# PCB.net
KiCad netlist of a schematic drawn in EAGLE
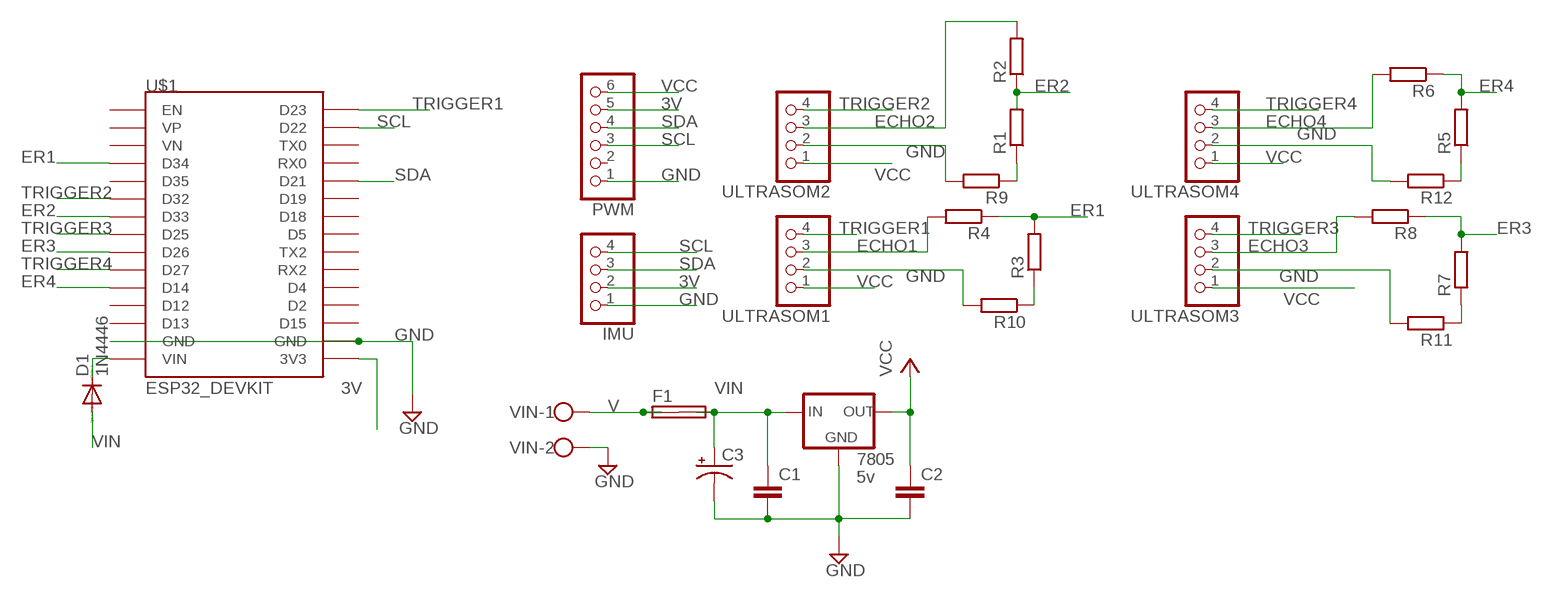
[diagram p0: schematic, sheet 1]

(export (version "E")
  (design (tool "Eeschema 10.0.6"))
  (components
    (comp (ref "7805")
      (value "5v")
      (footprint "eagle-import:78MXXS")
      (libsource (lib "eagle-import") (part "78MXXS"))
    )
    (comp (ref "C1")
      (value "C-EU025-024X044")
      (footprint "eagle-import:C025-024X044")
      (libsource (lib "eagle-import") (part "C-EU025-024X044"))
    )
    (comp (ref "C2")
      (value "C-EU025-024X044")
      (footprint "eagle-import:C025-024X044")
      (libsource (lib "eagle-import") (part "C-EU025-024X044"))
    )
    (comp (ref "C3")
      (value "CPOL-USE2-5")
      (footprint "eagle-import:E2-5")
      (libsource (lib "eagle-import") (part "CPOL-USE2-5"))
    )
    (comp (ref "D1")
      (value "1N4446")
      (footprint "eagle-import:DO35-10")
      (libsource (lib "eagle-import") (part "1N4446"))
    )
    (comp (ref "F1")
      (value "SHK20L")
      (footprint "eagle-import:SHK20L")
      (libsource (lib "eagle-import") (part "SHK20L"))
    )
    (comp (ref "IMU")
      (value "PINHD-1X4")
      (footprint "eagle-import:1X04")
      (libsource (lib "eagle-import") (part "PINHD-1X4"))
    )
    (comp (ref "PWM")
      (value "PINHD-1X6")
      (footprint "eagle-import:1X06")
      (libsource (lib "eagle-import") (part "PINHD-1X6"))
    )
    (comp (ref "R1")
      (value "R-EU_0207/7")
      (footprint "eagle-import:0207_7")
      (libsource (lib "eagle-import") (part "R-EU_0207/7"))
    )
    (comp (ref "R2")
      (value "R-EU_0207/7")
      (footprint "eagle-import:0207_7")
      (libsource (lib "eagle-import") (part "R-EU_0207/7"))
    )
    (comp (ref "R3")
      (value "R-EU_0207/7")
      (footprint "eagle-import:0207_7")
      (libsource (lib "eagle-import") (part "R-EU_0207/7"))
    )
    (comp (ref "R4")
      (value "R-EU_0207/7")
      (footprint "eagle-import:0207_7")
      (libsource (lib "eagle-import") (part "R-EU_0207/7"))
    )
    (comp (ref "R5")
      (value "R-EU_0207/7")
      (footprint "eagle-import:0207_7")
      (libsource (lib "eagle-import") (part "R-EU_0207/7"))
    )
    (comp (ref "R6")
      (value "R-EU_0207/7")
      (footprint "eagle-import:0207_7")
      (libsource (lib "eagle-import") (part "R-EU_0207/7"))
    )
    (comp (ref "R7")
      (value "R-EU_0207/7")
      (footprint "eagle-import:0207_7")
      (libsource (lib "eagle-import") (part "R-EU_0207/7"))
    )
    (comp (ref "R8")
      (value "R-EU_0207/7")
      (footprint "eagle-import:0207_7")
      (libsource (lib "eagle-import") (part "R-EU_0207/7"))
    )
    (comp (ref "R9")
      (value "R-EU_0207/7")
      (footprint "eagle-import:0207_7")
      (libsource (lib "eagle-import") (part "R-EU_0207/7"))
    )
    (comp (ref "R10")
      (value "R-EU_0207/7")
      (footprint "eagle-import:0207_7")
      (libsource (lib "eagle-import") (part "R-EU_0207/7"))
    )
    (comp (ref "R11")
      (value "R-EU_0207/7")
      (footprint "eagle-import:0207_7")
      (libsource (lib "eagle-import") (part "R-EU_0207/7"))
    )
    (comp (ref "R12")
      (value "R-EU_0207/7")
      (footprint "eagle-import:0207_7")
      (libsource (lib "eagle-import") (part "R-EU_0207/7"))
    )
    (comp (ref "U$1")
      (value "ESP32_DEVKIT")
      (footprint "eagle-import:ESP32_DEVKIT")
      (libsource (lib "eagle-import") (part "ESP32_DEVKIT"))
    )
    (comp (ref "ULTRASOM1")
      (value "PINHD-1X4")
      (footprint "eagle-import:1X04")
      (libsource (lib "eagle-import") (part "PINHD-1X4"))
    )
    (comp (ref "ULTRASOM2")
      (value "PINHD-1X4")
      (footprint "eagle-import:1X04")
      (libsource (lib "eagle-import") (part "PINHD-1X4"))
    )
    (comp (ref "ULTRASOM3")
      (value "PINHD-1X4")
      (footprint "eagle-import:1X04")
      (libsource (lib "eagle-import") (part "PINHD-1X4"))
    )
    (comp (ref "ULTRASOM4")
      (value "PINHD-1X4")
      (footprint "eagle-import:1X04")
      (libsource (lib "eagle-import") (part "PINHD-1X4"))
    )
    (comp (ref "VIN")
      (value "W237-102")
      (footprint "eagle-import:W237-102")
      (fields (field (name "MPN") "237-102"))
      (libsource (lib "eagle-import") (part "W237-102"))
    )
  )
  (nets
    (net (code "1") (name "/3V") (class "Default")
      (node (ref "IMU") (pin "2") (pinfunction "2_2") (pintype "passive"))
      (node (ref "PWM") (pin "5") (pinfunction "5_5") (pintype "passive"))
      (node (ref "U$1") (pin "3V3") (pinfunction "3V3_3V3") (pintype "bidirectional"))
    )
    (net (code "2") (name "/ECHO1") (class "Default")
      (node (ref "R4") (pin "2") (pinfunction "2_2") (pintype "passive"))
      (node (ref "ULTRASOM1") (pin "3") (pinfunction "3_3") (pintype "passive"))
    )
    (net (code "3") (name "/ECHO2") (class "Default")
      (node (ref "R2") (pin "2") (pinfunction "2_2") (pintype "passive"))
      (node (ref "ULTRASOM2") (pin "3") (pinfunction "3_3") (pintype "passive"))
    )
    (net (code "4") (name "/ECHO3") (class "Default")
      (node (ref "R8") (pin "2") (pinfunction "2_2") (pintype "passive"))
      (node (ref "ULTRASOM3") (pin "3") (pinfunction "3_3") (pintype "passive"))
    )
    (net (code "5") (name "/ECHO4") (class "Default")
      (node (ref "R6") (pin "2") (pinfunction "2_2") (pintype "passive"))
      (node (ref "ULTRASOM4") (pin "3") (pinfunction "3_3") (pintype "passive"))
    )
    (net (code "6") (name "/ER1") (class "Default")
      (node (ref "R3") (pin "2") (pinfunction "2_2") (pintype "passive"))
      (node (ref "R4") (pin "1") (pinfunction "1_1") (pintype "passive"))
      (node (ref "U$1") (pin "D34") (pinfunction "D34_D34") (pintype "bidirectional"))
    )
    (net (code "7") (name "/ER2") (class "Default")
      (node (ref "R1") (pin "2") (pinfunction "2_2") (pintype "passive"))
      (node (ref "R2") (pin "1") (pinfunction "1_1") (pintype "passive"))
      (node (ref "U$1") (pin "D33") (pinfunction "D33_D33") (pintype "bidirectional"))
    )
    (net (code "8") (name "/ER3") (class "Default")
      (node (ref "R7") (pin "2") (pinfunction "2_2") (pintype "passive"))
      (node (ref "R8") (pin "1") (pinfunction "1_1") (pintype "passive"))
      (node (ref "U$1") (pin "D26") (pinfunction "D26_D26") (pintype "bidirectional"))
    )
    (net (code "9") (name "/ER4") (class "Default")
      (node (ref "R5") (pin "2") (pinfunction "2_2") (pintype "passive"))
      (node (ref "R6") (pin "1") (pinfunction "1_1") (pintype "passive"))
      (node (ref "U$1") (pin "D14") (pinfunction "D14_D14") (pintype "bidirectional"))
    )
    (net (code "10") (name "/SCL") (class "Default")
      (node (ref "IMU") (pin "4") (pinfunction "4_4") (pintype "passive"))
      (node (ref "PWM") (pin "3") (pinfunction "3_3") (pintype "passive"))
      (node (ref "U$1") (pin "D22") (pinfunction "D22_D22") (pintype "bidirectional"))
    )
    (net (code "11") (name "/SDA") (class "Default")
      (node (ref "IMU") (pin "3") (pinfunction "3_3") (pintype "passive"))
      (node (ref "PWM") (pin "4") (pinfunction "4_4") (pintype "passive"))
      (node (ref "U$1") (pin "D21") (pinfunction "D21_D21") (pintype "bidirectional"))
    )
    (net (code "12") (name "/TRIGGER1") (class "Default")
      (node (ref "U$1") (pin "D23") (pinfunction "D23_D23") (pintype "bidirectional"))
      (node (ref "ULTRASOM1") (pin "4") (pinfunction "4_4") (pintype "passive"))
    )
    (net (code "13") (name "/TRIGGER2") (class "Default")
      (node (ref "U$1") (pin "D32") (pinfunction "D32_D32") (pintype "bidirectional"))
      (node (ref "ULTRASOM2") (pin "4") (pinfunction "4_4") (pintype "passive"))
    )
    (net (code "14") (name "/TRIGGER3") (class "Default")
      (node (ref "U$1") (pin "D25") (pinfunction "D25_D25") (pintype "bidirectional"))
      (node (ref "ULTRASOM3") (pin "4") (pinfunction "4_4") (pintype "passive"))
    )
    (net (code "15") (name "/TRIGGER4") (class "Default")
      (node (ref "U$1") (pin "D27") (pinfunction "D27_D27") (pintype "bidirectional"))
      (node (ref "ULTRASOM4") (pin "4") (pinfunction "4_4") (pintype "passive"))
    )
    (net (code "16") (name "/V") (class "Default")
      (node (ref "F1") (pin "1A") (pinfunction "1A_1A") (pintype "passive"))
      (node (ref "F1") (pin "1B") (pinfunction "1B_1B") (pintype "passive"))
      (node (ref "VIN") (pin "1") (pinfunction "KL_1") (pintype "passive"))
    )
    (net (code "17") (name "/VIN") (class "Default")
      (node (ref "7805") (pin "IN") (pinfunction "IN_IN") (pintype "input"))
      (node (ref "C1") (pin "1") (pinfunction "1_1") (pintype "passive"))
      (node (ref "C3") (pin "+") (pinfunction "+_+") (pintype "passive"))
      (node (ref "D1") (pin "A") (pinfunction "A_A") (pintype "passive"))
      (node (ref "F1") (pin "2A") (pinfunction "2A_2A") (pintype "passive"))
      (node (ref "F1") (pin "2B") (pinfunction "2B_2B") (pintype "passive"))
    )
    (net (code "18") (name "GND") (class "Default")
      (node (ref "7805") (pin "GND") (pinfunction "GND_GND") (pintype "input"))
      (node (ref "C1") (pin "2") (pinfunction "2_2") (pintype "passive"))
      (node (ref "C2") (pin "2") (pinfunction "2_2") (pintype "passive"))
      (node (ref "C3") (pin "-") (pinfunction "-_-") (pintype "passive"))
      (node (ref "IMU") (pin "1") (pinfunction "1_1") (pintype "passive"))
      (node (ref "PWM") (pin "1") (pinfunction "1_1") (pintype "passive"))
      (node (ref "R10") (pin "2") (pinfunction "2_2") (pintype "passive"))
      (node (ref "R11") (pin "2") (pinfunction "2_2") (pintype "passive"))
      (node (ref "R12") (pin "2") (pinfunction "2_2") (pintype "passive"))
      (node (ref "R9") (pin "2") (pinfunction "2_2") (pintype "passive"))
      (node (ref "U$1") (pin "GND@1") (pinfunction "GND_GND@1") (pintype "bidirectional"))
      (node (ref "U$1") (pin "GND@2") (pinfunction "GND_GND@2") (pintype "bidirectional"))
      (node (ref "ULTRASOM1") (pin "2") (pinfunction "2_2") (pintype "passive"))
      (node (ref "ULTRASOM2") (pin "2") (pinfunction "2_2") (pintype "passive"))
      (node (ref "ULTRASOM3") (pin "2") (pinfunction "2_2") (pintype "passive"))
      (node (ref "ULTRASOM4") (pin "2") (pinfunction "2_2") (pintype "passive"))
      (node (ref "VIN") (pin "2") (pinfunction "KL_2") (pintype "passive"))
    )
    (net (code "19") (name "Net-(D1-PadC)") (class "Default")
      (node (ref "D1") (pin "C") (pinfunction "C_C") (pintype "passive"))
      (node (ref "U$1") (pin "VIN") (pinfunction "VIN_VIN") (pintype "bidirectional"))
    )
    (net (code "20") (name "Net-(R1-Pad1)") (class "Default")
      (node (ref "R1") (pin "1") (pinfunction "1_1") (pintype "passive"))
      (node (ref "R9") (pin "1") (pinfunction "1_1") (pintype "passive"))
    )
    (net (code "21") (name "Net-(R10-Pad1)") (class "Default")
      (node (ref "R10") (pin "1") (pinfunction "1_1") (pintype "passive"))
      (node (ref "R3") (pin "1") (pinfunction "1_1") (pintype "passive"))
    )
    (net (code "22") (name "Net-(R11-Pad1)") (class "Default")
      (node (ref "R11") (pin "1") (pinfunction "1_1") (pintype "passive"))
      (node (ref "R7") (pin "1") (pinfunction "1_1") (pintype "passive"))
    )
    (net (code "23") (name "Net-(R12-Pad1)") (class "Default")
      (node (ref "R12") (pin "1") (pinfunction "1_1") (pintype "passive"))
      (node (ref "R5") (pin "1") (pinfunction "1_1") (pintype "passive"))
    )
    (net (code "24") (name "VCC") (class "Default")
      (node (ref "7805") (pin "OUT") (pinfunction "OUT_OUT") (pintype "passive"))
      (node (ref "C2") (pin "1") (pinfunction "1_1") (pintype "passive"))
      (node (ref "PWM") (pin "6") (pinfunction "6_6") (pintype "passive"))
      (node (ref "ULTRASOM1") (pin "1") (pinfunction "1_1") (pintype "passive"))
      (node (ref "ULTRASOM2") (pin "1") (pinfunction "1_1") (pintype "passive"))
      (node (ref "ULTRASOM3") (pin "1") (pinfunction "1_1") (pintype "passive"))
      (node (ref "ULTRASOM4") (pin "1") (pinfunction "1_1") (pintype "passive"))
    )
    (net (code "25") (name "unconnected-(PWM-Pad2)") (class "Default")
      (node (ref "PWM") (pin "2") (pinfunction "2_2") (pintype "passive"))
    )
    (net (code "26") (name "unconnected-(U$1-PadD2)") (class "Default")
      (node (ref "U$1") (pin "D2") (pinfunction "D2_D2") (pintype "bidirectional"))
    )
    (net (code "27") (name "unconnected-(U$1-PadD4)") (class "Default")
      (node (ref "U$1") (pin "D4") (pinfunction "D4_D4") (pintype "bidirectional"))
    )
    (net (code "28") (name "unconnected-(U$1-PadD5)") (class "Default")
      (node (ref "U$1") (pin "D5") (pinfunction "D5_D5") (pintype "bidirectional"))
    )
    (net (code "29") (name "unconnected-(U$1-PadD12)") (class "Default")
      (node (ref "U$1") (pin "D12") (pinfunction "D12_D12") (pintype "bidirectional"))
    )
    (net (code "30") (name "unconnected-(U$1-PadD13)") (class "Default")
      (node (ref "U$1") (pin "D13") (pinfunction "D13_D13") (pintype "bidirectional"))
    )
    (net (code "31") (name "unconnected-(U$1-PadD15)") (class "Default")
      (node (ref "U$1") (pin "D15") (pinfunction "D15_D15") (pintype "bidirectional"))
    )
    (net (code "32") (name "unconnected-(U$1-PadD18)") (class "Default")
      (node (ref "U$1") (pin "D18") (pinfunction "D18_D18") (pintype "bidirectional"))
    )
    (net (code "33") (name "unconnected-(U$1-PadD19)") (class "Default")
      (node (ref "U$1") (pin "D19") (pinfunction "D19_D19") (pintype "bidirectional"))
    )
    (net (code "34") (name "unconnected-(U$1-PadD35)") (class "Default")
      (node (ref "U$1") (pin "D35") (pinfunction "D35_D35") (pintype "bidirectional"))
    )
    (net (code "35") (name "unconnected-(U$1-PadEN)") (class "Default")
      (node (ref "U$1") (pin "EN") (pinfunction "EN_EN") (pintype "bidirectional"))
    )
    (net (code "36") (name "unconnected-(U$1-PadRX0)") (class "Default")
      (node (ref "U$1") (pin "RX0") (pinfunction "RX0_RX0") (pintype "bidirectional"))
    )
    (net (code "37") (name "unconnected-(U$1-PadRX2)") (class "Default")
      (node (ref "U$1") (pin "RX2") (pinfunction "RX2_RX2") (pintype "bidirectional"))
    )
    (net (code "38") (name "unconnected-(U$1-PadTX0)") (class "Default")
      (node (ref "U$1") (pin "TX0") (pinfunction "TX0_TX0") (pintype "bidirectional"))
    )
    (net (code "39") (name "unconnected-(U$1-PadTX2)") (class "Default")
      (node (ref "U$1") (pin "TX2") (pinfunction "TX2_TX2") (pintype "bidirectional"))
    )
    (net (code "40") (name "unconnected-(U$1-PadVN)") (class "Default")
      (node (ref "U$1") (pin "VN") (pinfunction "VN_VN") (pintype "bidirectional"))
    )
    (net (code "41") (name "unconnected-(U$1-PadVP)") (class "Default")
      (node (ref "U$1") (pin "VP") (pinfunction "VP_VP") (pintype "bidirectional"))
    )
  )
)
